# videoselector_2_1v.net
KiCad netlist of a schematic drawn in EAGLE
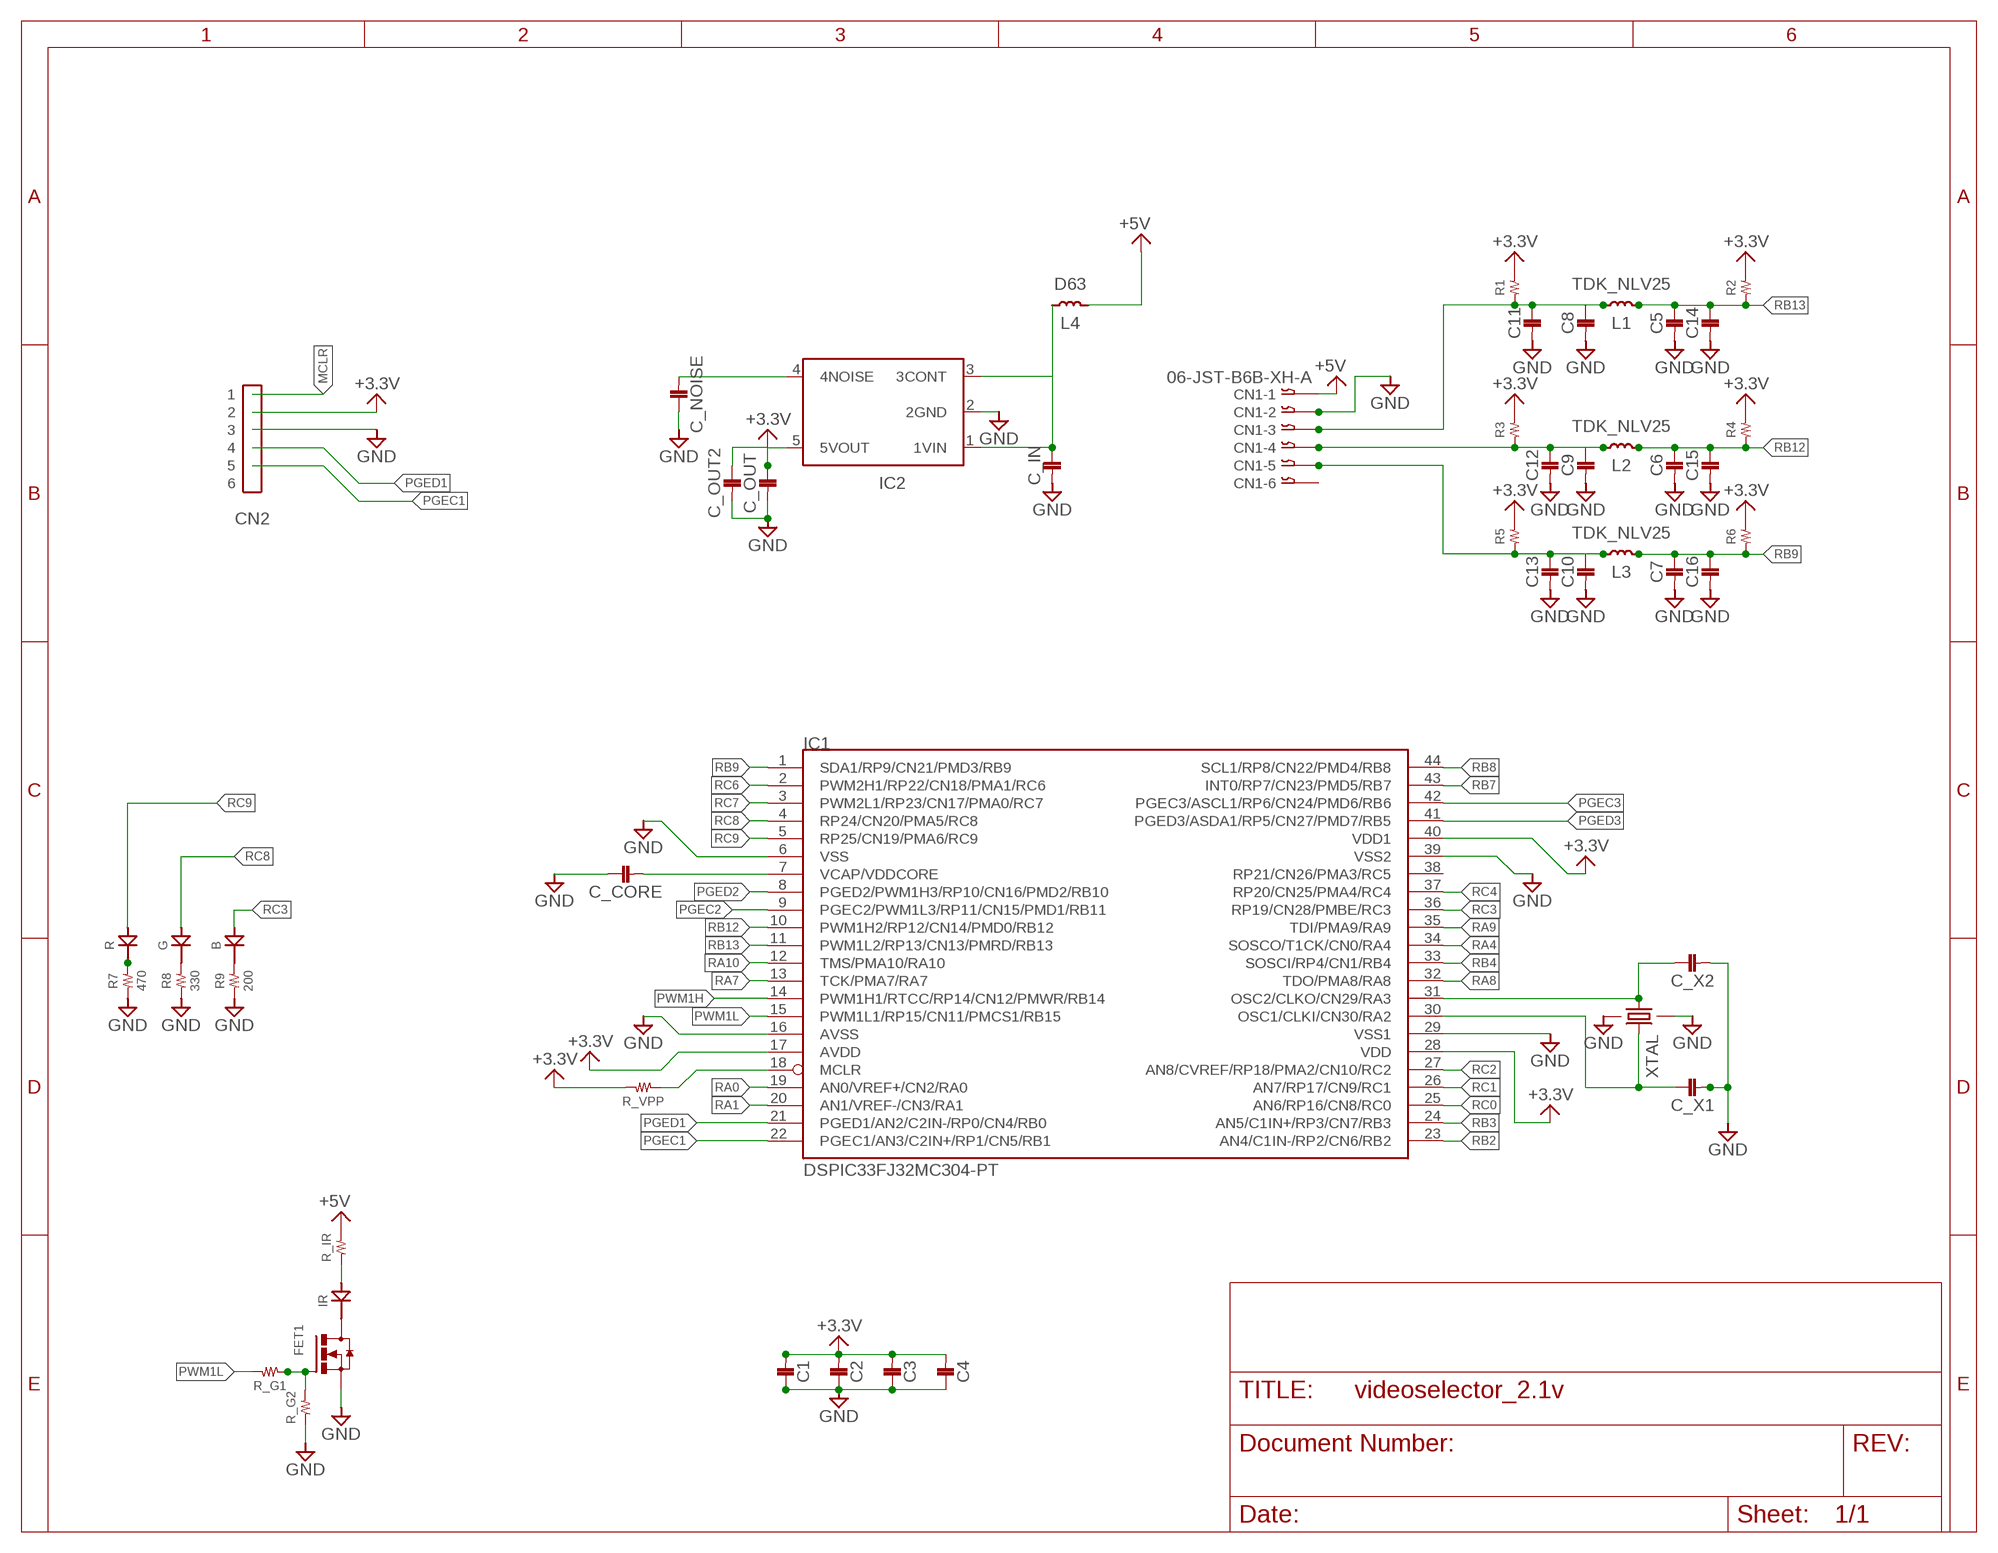
[diagram p0: schematic, sheet 1]

(export (version "E")
  (design (tool "Eeschema 10.0.6"))
  (components
    (comp (ref "B")
      (value "CHIPLED")
      (footprint "eagle-import:1608")
      (libsource (lib "eagle-import") (part "CHIPLED"))
    )
    (comp (ref "C1")
      (value "1608")
      (footprint "eagle-import:1608")
      (libsource (lib "eagle-import") (part "1608"))
    )
    (comp (ref "C2")
      (value "1608")
      (footprint "eagle-import:1608")
      (libsource (lib "eagle-import") (part "1608"))
    )
    (comp (ref "C3")
      (value "1608")
      (footprint "eagle-import:1608")
      (libsource (lib "eagle-import") (part "1608"))
    )
    (comp (ref "C4")
      (value "1608")
      (footprint "eagle-import:1608")
      (libsource (lib "eagle-import") (part "1608"))
    )
    (comp (ref "C5")
      (value "1608")
      (footprint "eagle-import:1608")
      (libsource (lib "eagle-import") (part "1608"))
    )
    (comp (ref "C6")
      (value "1608")
      (footprint "eagle-import:1608")
      (libsource (lib "eagle-import") (part "1608"))
    )
    (comp (ref "C7")
      (value "1608")
      (footprint "eagle-import:1608")
      (libsource (lib "eagle-import") (part "1608"))
    )
    (comp (ref "C8")
      (value "1608")
      (footprint "eagle-import:1608")
      (libsource (lib "eagle-import") (part "1608"))
    )
    (comp (ref "C9")
      (value "1608")
      (footprint "eagle-import:1608")
      (libsource (lib "eagle-import") (part "1608"))
    )
    (comp (ref "C10")
      (value "1608")
      (footprint "eagle-import:1608")
      (libsource (lib "eagle-import") (part "1608"))
    )
    (comp (ref "C11")
      (value "3225")
      (footprint "eagle-import:3225")
      (libsource (lib "eagle-import") (part "3225"))
    )
    (comp (ref "C12")
      (value "3225")
      (footprint "eagle-import:3225")
      (libsource (lib "eagle-import") (part "3225"))
    )
    (comp (ref "C13")
      (value "3225")
      (footprint "eagle-import:3225")
      (libsource (lib "eagle-import") (part "3225"))
    )
    (comp (ref "C14")
      (value "3225")
      (footprint "eagle-import:3225")
      (libsource (lib "eagle-import") (part "3225"))
    )
    (comp (ref "C15")
      (value "3225")
      (footprint "eagle-import:3225")
      (libsource (lib "eagle-import") (part "3225"))
    )
    (comp (ref "C16")
      (value "3225")
      (footprint "eagle-import:3225")
      (libsource (lib "eagle-import") (part "3225"))
    )
    (comp (ref "CN1")
      (value "06-JST-B6B-XH-A")
      (footprint "eagle-import:B6B-XH")
      (libsource (lib "eagle-import") (part "06-JST-B6B-XH-A"))
    )
    (comp (ref "CN2")
      (value "PIN_HEADER_6")
      (footprint "eagle-import:PIN_HEADER_6")
      (libsource (lib "eagle-import") (part "PIN_HEADER_6"))
    )
    (comp (ref "C_CORE")
      (value "2012")
      (footprint "eagle-import:2012")
      (libsource (lib "eagle-import") (part "2012"))
    )
    (comp (ref "C_IN")
      (value "1608")
      (footprint "eagle-import:1608")
      (libsource (lib "eagle-import") (part "1608"))
    )
    (comp (ref "C_NOISE")
      (value "1608")
      (footprint "eagle-import:1608")
      (libsource (lib "eagle-import") (part "1608"))
    )
    (comp (ref "C_OUT")
      (value "1608")
      (footprint "eagle-import:1608")
      (libsource (lib "eagle-import") (part "1608"))
    )
    (comp (ref "C_OUT2")
      (value "2012")
      (footprint "eagle-import:2012")
      (libsource (lib "eagle-import") (part "2012"))
    )
    (comp (ref "C_X1")
      (value "1608")
      (footprint "eagle-import:1608")
      (libsource (lib "eagle-import") (part "1608"))
    )
    (comp (ref "C_X2")
      (value "1608")
      (footprint "eagle-import:1608")
      (libsource (lib "eagle-import") (part "1608"))
    )
    (comp (ref "FET1")
      (value "ＩＲＬＭＬ６３４４")
      (footprint "eagle-import:SOT23")
      (libsource (lib "eagle-import") (part "ＩＲＬＭＬ６３４４"))
    )
    (comp (ref "G")
      (value "CHIPLED")
      (footprint "eagle-import:1608")
      (libsource (lib "eagle-import") (part "CHIPLED"))
    )
    (comp (ref "IC1")
      (value "DSPIC33FJ32MC304-PT")
      (footprint "eagle-import:TQFP44")
      (libsource (lib "eagle-import") (part "DSPIC33FJ32MC304-PT"))
    )
    (comp (ref "IC2")
      (value "TAR5SB")
      (footprint "eagle-import:SSOP5-P-0.95")
      (libsource (lib "eagle-import") (part "TAR5SB"))
    )
    (comp (ref "IR")
      (value "5MMLED")
      (footprint "eagle-import:5MM")
      (libsource (lib "eagle-import") (part "5MMLED"))
    )
    (comp (ref "L1")
      (value "TDK_NLV25")
      (footprint "eagle-import:TDK_NLV")
      (libsource (lib "eagle-import") (part "TDK_NLV25"))
    )
    (comp (ref "L2")
      (value "TDK_NLV25")
      (footprint "eagle-import:TDK_NLV")
      (libsource (lib "eagle-import") (part "TDK_NLV25"))
    )
    (comp (ref "L3")
      (value "TDK_NLV25")
      (footprint "eagle-import:TDK_NLV")
      (libsource (lib "eagle-import") (part "TDK_NLV25"))
    )
    (comp (ref "L4")
      (value "D63")
      (footprint "eagle-import:TOKO")
      (libsource (lib "eagle-import") (part "D63"))
    )
    (comp (ref "R")
      (value "CHIPLED")
      (footprint "eagle-import:1608")
      (libsource (lib "eagle-import") (part "CHIPLED"))
    )
    (comp (ref "R1")
      (value "RESISTOR__SMD")
      (footprint "eagle-import:1608")
      (libsource (lib "eagle-import") (part "RESISTOR__SMD"))
    )
    (comp (ref "R2")
      (value "RESISTOR__SMD")
      (footprint "eagle-import:1608")
      (libsource (lib "eagle-import") (part "RESISTOR__SMD"))
    )
    (comp (ref "R3")
      (value "RESISTOR__SMD")
      (footprint "eagle-import:1608")
      (libsource (lib "eagle-import") (part "RESISTOR__SMD"))
    )
    (comp (ref "R4")
      (value "RESISTOR__SMD")
      (footprint "eagle-import:1608")
      (libsource (lib "eagle-import") (part "RESISTOR__SMD"))
    )
    (comp (ref "R5")
      (value "RESISTOR__SMD")
      (footprint "eagle-import:1608")
      (libsource (lib "eagle-import") (part "RESISTOR__SMD"))
    )
    (comp (ref "R6")
      (value "RESISTOR__SMD")
      (footprint "eagle-import:1608")
      (libsource (lib "eagle-import") (part "RESISTOR__SMD"))
    )
    (comp (ref "R7")
      (value "470")
      (footprint "eagle-import:1608")
      (libsource (lib "eagle-import") (part "RESISTOR__SMD"))
    )
    (comp (ref "R8")
      (value "330")
      (footprint "eagle-import:1608")
      (libsource (lib "eagle-import") (part "RESISTOR__SMD"))
    )
    (comp (ref "R9")
      (value "200")
      (footprint "eagle-import:1608")
      (libsource (lib "eagle-import") (part "RESISTOR__SMD"))
    )
    (comp (ref "R_G1")
      (value "RESISTOR__SMD")
      (footprint "eagle-import:1608")
      (libsource (lib "eagle-import") (part "RESISTOR__SMD"))
    )
    (comp (ref "R_G2")
      (value "RESISTOR__SMD")
      (footprint "eagle-import:1608")
      (libsource (lib "eagle-import") (part "RESISTOR__SMD"))
    )
    (comp (ref "R_IR")
      (value "RESISTOR__SMD")
      (footprint "eagle-import:1608")
      (libsource (lib "eagle-import") (part "RESISTOR__SMD"))
    )
    (comp (ref "R_VPP")
      (value "RESISTOR__SMD")
      (footprint "eagle-import:1608")
      (libsource (lib "eagle-import") (part "RESISTOR__SMD"))
    )
    (comp (ref "XTAL")
      (value "FA-238")
      (footprint "eagle-import:FA-238")
      (libsource (lib "eagle-import") (part "FA-238"))
    )
  )
  (nets
    (net (code "1") (name "+3.3V") (class "Default")
      (node (ref "C1") (pin "P$2") (pinfunction "2_P$2") (pintype "passive"))
      (node (ref "C2") (pin "P$2") (pinfunction "2_P$2") (pintype "passive"))
      (node (ref "C3") (pin "P$2") (pinfunction "2_P$2") (pintype "passive"))
      (node (ref "C4") (pin "P$2") (pinfunction "2_P$2") (pintype "passive"))
      (node (ref "CN2") (pin "2") (pinfunction "2_2") (pintype "bidirectional"))
      (node (ref "C_OUT") (pin "P$1") (pinfunction "1_P$1") (pintype "passive"))
      (node (ref "C_OUT2") (pin "1") (pinfunction "1_1") (pintype "passive"))
      (node (ref "IC1") (pin "17") (pinfunction "AVDD_17") (pintype "power_in"))
      (node (ref "IC1") (pin "28") (pinfunction "VDD_28") (pintype "power_in"))
      (node (ref "IC1") (pin "40") (pinfunction "VDD1_40") (pintype "power_in"))
      (node (ref "IC2") (pin "5") (pinfunction "5VOUT_5") (pintype "bidirectional"))
      (node (ref "R1") (pin "2") (pinfunction "P$2_2") (pintype "passive"))
      (node (ref "R2") (pin "2") (pinfunction "P$2_2") (pintype "passive"))
      (node (ref "R3") (pin "2") (pinfunction "P$2_2") (pintype "passive"))
      (node (ref "R4") (pin "2") (pinfunction "P$2_2") (pintype "passive"))
      (node (ref "R5") (pin "2") (pinfunction "P$2_2") (pintype "passive"))
      (node (ref "R6") (pin "2") (pinfunction "P$2_2") (pintype "passive"))
      (node (ref "R_VPP") (pin "2") (pinfunction "P$2_2") (pintype "passive"))
    )
    (net (code "2") (name "+5V") (class "Default")
      (node (ref "CN1") (pin "P$1") (pinfunction "1_P$1") (pintype "passive"))
      (node (ref "L4") (pin "2") (pinfunction "2_2") (pintype "passive"))
      (node (ref "R_IR") (pin "2") (pinfunction "P$2_2") (pintype "passive"))
    )
    (net (code "3") (name "GND") (class "Default")
      (node (ref "C1") (pin "P$1") (pinfunction "1_P$1") (pintype "passive"))
      (node (ref "C10") (pin "P$2") (pinfunction "2_P$2") (pintype "passive"))
      (node (ref "C11") (pin "P$2") (pinfunction "2_P$2") (pintype "passive"))
      (node (ref "C12") (pin "P$2") (pinfunction "2_P$2") (pintype "passive"))
      (node (ref "C13") (pin "P$2") (pinfunction "2_P$2") (pintype "passive"))
      (node (ref "C14") (pin "P$2") (pinfunction "2_P$2") (pintype "passive"))
      (node (ref "C15") (pin "P$2") (pinfunction "2_P$2") (pintype "passive"))
      (node (ref "C16") (pin "P$2") (pinfunction "2_P$2") (pintype "passive"))
      (node (ref "C2") (pin "P$1") (pinfunction "1_P$1") (pintype "passive"))
      (node (ref "C3") (pin "P$1") (pinfunction "1_P$1") (pintype "passive"))
      (node (ref "C4") (pin "P$1") (pinfunction "1_P$1") (pintype "passive"))
      (node (ref "C5") (pin "P$2") (pinfunction "2_P$2") (pintype "passive"))
      (node (ref "C6") (pin "P$2") (pinfunction "2_P$2") (pintype "passive"))
      (node (ref "C7") (pin "P$2") (pinfunction "2_P$2") (pintype "passive"))
      (node (ref "C8") (pin "P$2") (pinfunction "2_P$2") (pintype "passive"))
      (node (ref "C9") (pin "P$2") (pinfunction "2_P$2") (pintype "passive"))
      (node (ref "CN1") (pin "P$2") (pinfunction "1_P$2") (pintype "passive"))
      (node (ref "CN2") (pin "3") (pinfunction "3_3") (pintype "bidirectional"))
      (node (ref "C_CORE") (pin "1") (pinfunction "1_1") (pintype "passive"))
      (node (ref "C_IN") (pin "P$2") (pinfunction "2_P$2") (pintype "passive"))
      (node (ref "C_NOISE") (pin "P$1") (pinfunction "1_P$1") (pintype "passive"))
      (node (ref "C_OUT") (pin "P$2") (pinfunction "2_P$2") (pintype "passive"))
      (node (ref "C_OUT2") (pin "2") (pinfunction "2_2") (pintype "passive"))
      (node (ref "C_X1") (pin "P$2") (pinfunction "2_P$2") (pintype "passive"))
      (node (ref "C_X2") (pin "P$2") (pinfunction "2_P$2") (pintype "passive"))
      (node (ref "FET1") (pin "2") (pinfunction "S_2") (pintype "passive"))
      (node (ref "IC1") (pin "16") (pinfunction "AVSS_16") (pintype "power_in"))
      (node (ref "IC1") (pin "29") (pinfunction "VSS1_29") (pintype "power_in"))
      (node (ref "IC1") (pin "39") (pinfunction "VSS2_39") (pintype "power_in"))
      (node (ref "IC1") (pin "6") (pinfunction "VSS_6") (pintype "power_in"))
      (node (ref "IC2") (pin "2") (pinfunction "2GND_2") (pintype "bidirectional"))
      (node (ref "R7") (pin "1") (pinfunction "P$1_1") (pintype "passive"))
      (node (ref "R8") (pin "1") (pinfunction "P$1_1") (pintype "passive"))
      (node (ref "R9") (pin "1") (pinfunction "P$1_1") (pintype "passive"))
      (node (ref "R_G2") (pin "1") (pinfunction "P$1_1") (pintype "passive"))
      (node (ref "XTAL") (pin "2") (pinfunction "2_2") (pintype "bidirectional"))
      (node (ref "XTAL") (pin "4") (pinfunction "4_4") (pintype "bidirectional"))
    )
    (net (code "4") (name "MCLR") (class "Default")
      (node (ref "CN2") (pin "1") (pinfunction "1_1") (pintype "bidirectional"))
      (node (ref "IC1") (pin "18") (pinfunction "MCLR_18") (pintype "input"))
      (node (ref "R_VPP") (pin "1") (pinfunction "P$1_1") (pintype "passive"))
    )
    (net (code "5") (name "Net-(B-K)") (class "Default")
      (node (ref "B") (pin "2") (pinfunction "K_2") (pintype "bidirectional"))
      (node (ref "R9") (pin "2") (pinfunction "P$2_2") (pintype "passive"))
    )
    (net (code "6") (name "Net-(C10-1)") (class "Default")
      (node (ref "C10") (pin "P$1") (pinfunction "1_P$1") (pintype "passive"))
      (node (ref "C13") (pin "P$1") (pinfunction "1_P$1") (pintype "passive"))
      (node (ref "CN1") (pin "P$5") (pinfunction "1_P$5") (pintype "passive"))
      (node (ref "L3") (pin "P$1") (pinfunction "1_P$1") (pintype "passive"))
      (node (ref "R5") (pin "1") (pinfunction "P$1_1") (pintype "passive"))
    )
    (net (code "7") (name "Net-(C11-1)") (class "Default")
      (node (ref "C11") (pin "P$1") (pinfunction "1_P$1") (pintype "passive"))
      (node (ref "C8") (pin "P$1") (pinfunction "1_P$1") (pintype "passive"))
      (node (ref "CN1") (pin "P$3") (pinfunction "1_P$3") (pintype "passive"))
      (node (ref "L1") (pin "P$1") (pinfunction "1_P$1") (pintype "passive"))
      (node (ref "R1") (pin "1") (pinfunction "P$1_1") (pintype "passive"))
    )
    (net (code "8") (name "Net-(C12-1)") (class "Default")
      (node (ref "C12") (pin "P$1") (pinfunction "1_P$1") (pintype "passive"))
      (node (ref "C9") (pin "P$1") (pinfunction "1_P$1") (pintype "passive"))
      (node (ref "CN1") (pin "P$4") (pinfunction "1_P$4") (pintype "passive"))
      (node (ref "L2") (pin "P$1") (pinfunction "1_P$1") (pintype "passive"))
      (node (ref "R3") (pin "1") (pinfunction "P$1_1") (pintype "passive"))
    )
    (net (code "9") (name "Net-(C_IN-1)") (class "Default")
      (node (ref "C_IN") (pin "P$1") (pinfunction "1_P$1") (pintype "passive"))
      (node (ref "IC2") (pin "1") (pinfunction "1VIN_1") (pintype "bidirectional"))
      (node (ref "IC2") (pin "3") (pinfunction "3CONT_3") (pintype "bidirectional"))
      (node (ref "L4") (pin "1") (pinfunction "1_1") (pintype "passive"))
    )
    (net (code "10") (name "Net-(C_NOISE-2)") (class "Default")
      (node (ref "C_NOISE") (pin "P$2") (pinfunction "2_P$2") (pintype "passive"))
      (node (ref "IC2") (pin "4") (pinfunction "4NOISE_4") (pintype "bidirectional"))
    )
    (net (code "11") (name "Net-(C_X1-1)") (class "Default")
      (node (ref "C_X1") (pin "P$1") (pinfunction "1_P$1") (pintype "passive"))
      (node (ref "IC1") (pin "30") (pinfunction "OSC1/CLKI/CN30/RA2_30") (pintype "bidirectional"))
      (node (ref "XTAL") (pin "3") (pinfunction "3_3") (pintype "passive"))
    )
    (net (code "12") (name "Net-(C_X2-1)") (class "Default")
      (node (ref "C_X2") (pin "P$1") (pinfunction "1_P$1") (pintype "passive"))
      (node (ref "IC1") (pin "31") (pinfunction "OSC2/CLKO/CN29/RA3_31") (pintype "bidirectional"))
      (node (ref "XTAL") (pin "1") (pinfunction "1_1") (pintype "passive"))
    )
    (net (code "13") (name "Net-(FET1-D)") (class "Default")
      (node (ref "FET1") (pin "3") (pinfunction "D_3") (pintype "passive"))
      (node (ref "IR") (pin "K") (pinfunction "K_K") (pintype "bidirectional"))
    )
    (net (code "14") (name "Net-(FET1-G)") (class "Default")
      (node (ref "FET1") (pin "1") (pinfunction "G_1") (pintype "passive"))
      (node (ref "R_G1") (pin "1") (pinfunction "P$1_1") (pintype "passive"))
      (node (ref "R_G2") (pin "2") (pinfunction "P$2_2") (pintype "passive"))
    )
    (net (code "15") (name "Net-(G-K)") (class "Default")
      (node (ref "G") (pin "2") (pinfunction "K_2") (pintype "bidirectional"))
      (node (ref "R8") (pin "2") (pinfunction "P$2_2") (pintype "passive"))
    )
    (net (code "16") (name "Net-(IC1-VCAP{slash}VDDCORE)") (class "Default")
      (node (ref "C_CORE") (pin "2") (pinfunction "2_2") (pintype "passive"))
      (node (ref "IC1") (pin "7") (pinfunction "VCAP/VDDCORE_7") (pintype "power_in"))
    )
    (net (code "17") (name "Net-(R-K)") (class "Default")
      (node (ref "R") (pin "2") (pinfunction "K_2") (pintype "bidirectional"))
      (node (ref "R7") (pin "2") (pinfunction "P$2_2") (pintype "passive"))
    )
    (net (code "18") (name "Net-(R_IR-P$1)") (class "Default")
      (node (ref "IR") (pin "A") (pinfunction "A_A") (pintype "bidirectional"))
      (node (ref "R_IR") (pin "1") (pinfunction "P$1_1") (pintype "passive"))
    )
    (net (code "19") (name "PGEC1") (class "Default")
      (node (ref "CN2") (pin "5") (pinfunction "5_5") (pintype "bidirectional"))
      (node (ref "IC1") (pin "22") (pinfunction "PGEC1/AN3/C2IN+/RP1/CN5/RB1_22") (pintype "bidirectional"))
    )
    (net (code "20") (name "PGEC2") (class "Default")
      (node (ref "IC1") (pin "9") (pinfunction "PGEC2/PWM1L3/RP11/CN15/PMD1/RB11_9") (pintype "bidirectional"))
    )
    (net (code "21") (name "PGEC3") (class "Default")
      (node (ref "IC1") (pin "42") (pinfunction "PGEC3/ASCL1/RP6/CN24/PMD6/RB6_42") (pintype "bidirectional"))
    )
    (net (code "22") (name "PGED1") (class "Default")
      (node (ref "CN2") (pin "4") (pinfunction "4_4") (pintype "bidirectional"))
      (node (ref "IC1") (pin "21") (pinfunction "PGED1/AN2/C2IN-/RP0/CN4/RB0_21") (pintype "bidirectional"))
    )
    (net (code "23") (name "PGED2") (class "Default")
      (node (ref "IC1") (pin "8") (pinfunction "PGED2/PWM1H3/RP10/CN16/PMD2/RB10_8") (pintype "bidirectional"))
    )
    (net (code "24") (name "PGED3") (class "Default")
      (node (ref "IC1") (pin "41") (pinfunction "PGED3/ASDA1/RP5/CN27/PMD7/RB5_41") (pintype "bidirectional"))
    )
    (net (code "25") (name "PWM1H") (class "Default")
      (node (ref "IC1") (pin "14") (pinfunction "PWM1H1/RTCC/RP14/CN12/PMWR/RB14_14") (pintype "bidirectional"))
    )
    (net (code "26") (name "PWM1L") (class "Default")
      (node (ref "IC1") (pin "15") (pinfunction "PWM1L1/RP15/CN11/PMCS1/RB15_15") (pintype "bidirectional"))
      (node (ref "R_G1") (pin "2") (pinfunction "P$2_2") (pintype "passive"))
    )
    (net (code "27") (name "RA0") (class "Default")
      (node (ref "IC1") (pin "19") (pinfunction "AN0/VREF+/CN2/RA0_19") (pintype "bidirectional"))
    )
    (net (code "28") (name "RA1") (class "Default")
      (node (ref "IC1") (pin "20") (pinfunction "AN1/VREF-/CN3/RA1_20") (pintype "bidirectional"))
    )
    (net (code "29") (name "RA4") (class "Default")
      (node (ref "IC1") (pin "34") (pinfunction "SOSCO/T1CK/CN0/RA4_34") (pintype "bidirectional"))
    )
    (net (code "30") (name "RA7") (class "Default")
      (node (ref "IC1") (pin "13") (pinfunction "TCK/PMA7/RA7_13") (pintype "bidirectional"))
    )
    (net (code "31") (name "RA8") (class "Default")
      (node (ref "IC1") (pin "32") (pinfunction "TDO/PMA8/RA8_32") (pintype "bidirectional"))
    )
    (net (code "32") (name "RA9") (class "Default")
      (node (ref "IC1") (pin "35") (pinfunction "TDI/PMA9/RA9_35") (pintype "bidirectional"))
    )
    (net (code "33") (name "RA10") (class "Default")
      (node (ref "IC1") (pin "12") (pinfunction "TMS/PMA10/RA10_12") (pintype "bidirectional"))
    )
    (net (code "34") (name "RB2") (class "Default")
      (node (ref "IC1") (pin "23") (pinfunction "AN4/C1IN-/RP2/CN6/RB2_23") (pintype "bidirectional"))
    )
    (net (code "35") (name "RB3") (class "Default")
      (node (ref "IC1") (pin "24") (pinfunction "AN5/C1IN+/RP3/CN7/RB3_24") (pintype "bidirectional"))
    )
    (net (code "36") (name "RB4") (class "Default")
      (node (ref "IC1") (pin "33") (pinfunction "SOSCI/RP4/CN1/RB4_33") (pintype "bidirectional"))
    )
    (net (code "37") (name "RB7") (class "Default")
      (node (ref "IC1") (pin "43") (pinfunction "INT0/RP7/CN23/PMD5/RB7_43") (pintype "bidirectional"))
    )
    (net (code "38") (name "RB8") (class "Default")
      (node (ref "IC1") (pin "44") (pinfunction "SCL1/RP8/CN22/PMD4/RB8_44") (pintype "bidirectional"))
    )
    (net (code "39") (name "RB9") (class "Default")
      (node (ref "C16") (pin "P$1") (pinfunction "1_P$1") (pintype "passive"))
      (node (ref "C7") (pin "P$1") (pinfunction "1_P$1") (pintype "passive"))
      (node (ref "IC1") (pin "1") (pinfunction "SDA1/RP9/CN21/PMD3/RB9_1") (pintype "bidirectional"))
      (node (ref "L3") (pin "P$2") (pinfunction "2_P$2") (pintype "passive"))
      (node (ref "R6") (pin "1") (pinfunction "P$1_1") (pintype "passive"))
    )
    (net (code "40") (name "RB12") (class "Default")
      (node (ref "C15") (pin "P$1") (pinfunction "1_P$1") (pintype "passive"))
      (node (ref "C6") (pin "P$1") (pinfunction "1_P$1") (pintype "passive"))
      (node (ref "IC1") (pin "10") (pinfunction "PWM1H2/RP12/CN14/PMD0/RB12_10") (pintype "bidirectional"))
      (node (ref "L2") (pin "P$2") (pinfunction "2_P$2") (pintype "passive"))
      (node (ref "R4") (pin "1") (pinfunction "P$1_1") (pintype "passive"))
    )
    (net (code "41") (name "RB13") (class "Default")
      (node (ref "C14") (pin "P$1") (pinfunction "1_P$1") (pintype "passive"))
      (node (ref "C5") (pin "P$1") (pinfunction "1_P$1") (pintype "passive"))
      (node (ref "IC1") (pin "11") (pinfunction "PWM1L2/RP13/CN13/PMRD/RB13_11") (pintype "bidirectional"))
      (node (ref "L1") (pin "P$2") (pinfunction "2_P$2") (pintype "passive"))
      (node (ref "R2") (pin "1") (pinfunction "P$1_1") (pintype "passive"))
    )
    (net (code "42") (name "RC0") (class "Default")
      (node (ref "IC1") (pin "25") (pinfunction "AN6/RP16/CN8/RC0_25") (pintype "bidirectional"))
    )
    (net (code "43") (name "RC1") (class "Default")
      (node (ref "IC1") (pin "26") (pinfunction "AN7/RP17/CN9/RC1_26") (pintype "bidirectional"))
    )
    (net (code "44") (name "RC2") (class "Default")
      (node (ref "IC1") (pin "27") (pinfunction "AN8/CVREF/RP18/PMA2/CN10/RC2_27") (pintype "bidirectional"))
    )
    (net (code "45") (name "RC3") (class "Default")
      (node (ref "B") (pin "1") (pinfunction "A_1") (pintype "bidirectional"))
      (node (ref "IC1") (pin "36") (pinfunction "RP19/CN28/PMBE/RC3_36") (pintype "bidirectional"))
    )
    (net (code "46") (name "RC4") (class "Default")
      (node (ref "IC1") (pin "37") (pinfunction "RP20/CN25/PMA4/RC4_37") (pintype "bidirectional"))
    )
    (net (code "47") (name "RC6") (class "Default")
      (node (ref "IC1") (pin "2") (pinfunction "PWM2H1/RP22/CN18/PMA1/RC6_2") (pintype "bidirectional"))
    )
    (net (code "48") (name "RC7") (class "Default")
      (node (ref "IC1") (pin "3") (pinfunction "PWM2L1/RP23/CN17/PMA0/RC7_3") (pintype "bidirectional"))
    )
    (net (code "49") (name "RC8") (class "Default")
      (node (ref "G") (pin "1") (pinfunction "A_1") (pintype "bidirectional"))
      (node (ref "IC1") (pin "4") (pinfunction "RP24/CN20/PMA5/RC8_4") (pintype "bidirectional"))
    )
    (net (code "50") (name "RC9") (class "Default")
      (node (ref "IC1") (pin "5") (pinfunction "RP25/CN19/PMA6/RC9_5") (pintype "bidirectional"))
      (node (ref "R") (pin "1") (pinfunction "A_1") (pintype "bidirectional"))
    )
    (net (code "51") (name "unconnected-(CN1F-1-PadP$6)") (class "Default")
      (node (ref "CN1") (pin "P$6") (pinfunction "1_P$6") (pintype "passive"))
    )
    (net (code "52") (name "unconnected-(CN2-Pad6)") (class "Default")
      (node (ref "CN2") (pin "6") (pinfunction "6_6") (pintype "bidirectional"))
    )
    (net (code "53") (name "unconnected-(IC1-RP21{slash}CN26{slash}PMA3{slash}RC5-Pad38)") (class "Default")
      (node (ref "IC1") (pin "38") (pinfunction "RP21/CN26/PMA3/RC5_38") (pintype "bidirectional"))
    )
  )
)
